# TCA785-V.net
KiCad netlist of a schematic drawn in Altium Designer
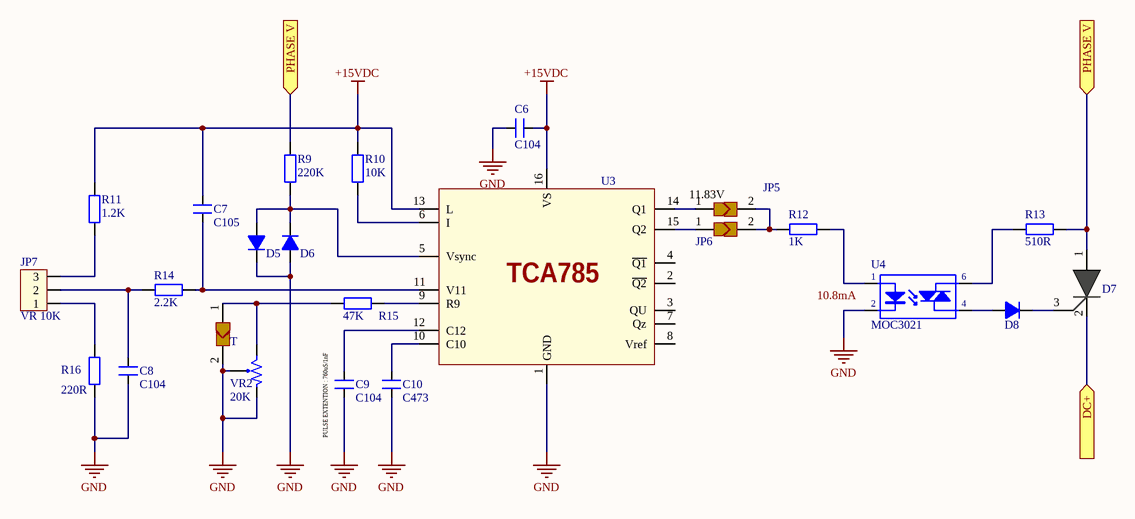
[diagram p0: TCA785-V.SchDoc]

(export (version "E")
  (design (tool "Eeschema 10.0.6"))
  (components
    (comp (ref "C6")
      (value "C104")
      (footprint "CN2-O")
      (description "CAP-gom")
      (libsource (lib "Sang_Library") (part "CAP-gom"))
    )
    (comp (ref "C7")
      (value "C105")
      (footprint "CN2-O")
      (description "CAP-gom")
      (libsource (lib "Sang_Library") (part "CAP-gom"))
    )
    (comp (ref "C8")
      (value "C104")
      (footprint "CN2-O")
      (description "CAP-gom")
      (libsource (lib "Sang_Library") (part "CAP-gom"))
    )
    (comp (ref "C9")
      (value "C104")
      (footprint "CN2-O")
      (description "CAP-gom")
      (libsource (lib "Sang_Library") (part "CAP-gom"))
    )
    (comp (ref "C10")
      (value "C473")
      (footprint "CN2-O")
      (description "CAP-gom")
      (libsource (lib "Sang_Library") (part "CAP-gom"))
    )
    (comp (ref "D5")
      (value "Diode  1N4007")
      (footprint "DO41-1A")
      (description "Diode 1A")
      (libsource (lib "Sang_Library") (part "Diode  1N4007"))
    )
    (comp (ref "D6")
      (value "Diode  1N4007")
      (footprint "DO41-1A")
      (description "Diode 1A")
      (libsource (lib "Sang_Library") (part "Diode  1N4007"))
    )
    (comp (ref "D7") (value "SCR") (footprint "TO-220") (libsource (lib "Huan") (part "BT151")))
    (comp (ref "D8")
      (value "Diode  1N4007")
      (footprint "DO41-1A")
      (description "Diode 1A")
      (libsource (lib "Sang_Library") (part "Diode  1N4007"))
    )
    (comp (ref "JP5")
      (value "PAD_Sellect")
      (footprint "PAD Select")
      (libsource (lib "Huan") (part "PAD_Sellect"))
    )
    (comp (ref "JP6")
      (value "PAD_Sellect")
      (footprint "PAD Select")
      (libsource (lib "Huan") (part "PAD_Sellect"))
    )
    (comp (ref "JP7")
      (value "VR 10K")
      (footprint "CON3")
      (description "Connector 3")
      (libsource (lib "syhaunguyen") (part "Con3"))
    )
    (comp (ref "R9")
      (value "220K")
      (footprint "R1/4W")
      (description "Resistor 1/4W")
      (libsource (lib "Sang_Library") (part "R1/4W"))
    )
    (comp (ref "R10")
      (value "10K")
      (footprint "R1/4W")
      (description "Resistor 1/4W")
      (libsource (lib "Sang_Library") (part "R1/4W"))
    )
    (comp (ref "R11")
      (value "1.2K")
      (footprint "R1/4W")
      (description "Resistor 1/4W")
      (libsource (lib "Sang_Library") (part "R1/4W"))
    )
    (comp (ref "R12")
      (value "1K")
      (footprint "R1/4W")
      (description "Resistor 1/4W")
      (libsource (lib "Sang_Library") (part "R1/4W"))
    )
    (comp (ref "R13")
      (value "510R")
      (footprint "R1/4W")
      (description "Resistor 1/4W")
      (libsource (lib "Sang_Library") (part "R1/4W"))
    )
    (comp (ref "R14")
      (value "2.2K")
      (footprint "R1/4W")
      (description "Resistor 1/4W")
      (libsource (lib "Sang_Library") (part "R1/4W"))
    )
    (comp (ref "R15")
      (value "47K")
      (footprint "R1/4W")
      (description "Resistor 1/4W")
      (libsource (lib "Sang_Library") (part "R1/4W"))
    )
    (comp (ref "R16")
      (value "220R")
      (footprint "R1/4W")
      (description "Resistor 1/4W")
      (libsource (lib "Sang_Library") (part "R1/4W"))
    )
    (comp (ref "T")
      (value "PAD_Sellect")
      (footprint "PAD Select")
      (libsource (lib "Huan") (part "PAD_Sellect"))
    )
    (comp (ref "U3") (value "TCA785Q") (footprint "DIP-16") (libsource (lib "Huan") (part "TCA785Q")))
    (comp (ref "U4")
      (value "MOC3021")
      (footprint "DIP6/W0.3 - MOC3021")
      (description "Single Opto")
      (libsource (lib "Sang_Library") (part "MOC3021"))
    )
    (comp (ref "VR2")
      (value "20K")
      (footprint "VR")
      (description "Var Resistor RM065")
      (libsource (lib "Sang_Library") (part "VR"))
    )
  )
  (nets
    (net (code "1") (name "+15VDC") (class "Default")
      (node (ref "C6") (pin "2") (pinfunction "2_2") (pintype "passive"))
      (node (ref "C7") (pin "2") (pinfunction "2_2") (pintype "passive"))
      (node (ref "R10") (pin "1") (pinfunction "1_1") (pintype "passive"))
      (node (ref "R11") (pin "2") (pinfunction "2_2") (pintype "passive"))
      (node (ref "U3") (pin "13") (pinfunction "L_13") (pintype "passive"))
      (node (ref "U3") (pin "16") (pinfunction "VS_16") (pintype "passive"))
    )
    (net (code "3") (name "/DC+") (class "Default")
      (node (ref "D7") (pin "2") (pinfunction "K_2") (pintype "passive"))
    )
    (net (code "4") (name "/PHASE V") (class "Default")
      (node (ref "D7") (pin "1") (pinfunction "A_1") (pintype "passive"))
      (node (ref "R13") (pin "1") (pinfunction "1_1") (pintype "passive"))
      (node (ref "R9") (pin "1") (pinfunction "1_1") (pintype "passive"))
    )
    (net (code "5") (name "GND") (class "Default")
      (node (ref "C10") (pin "1") (pinfunction "1_1") (pintype "passive"))
      (node (ref "C6") (pin "1") (pinfunction "1_1") (pintype "passive"))
      (node (ref "C8") (pin "1") (pinfunction "1_1") (pintype "passive"))
      (node (ref "C9") (pin "1") (pinfunction "1_1") (pintype "passive"))
      (node (ref "D5") (pin "2") (pinfunction "2_2") (pintype "passive"))
      (node (ref "D6") (pin "1") (pinfunction "1_1") (pintype "passive"))
      (node (ref "R16") (pin "1") (pinfunction "1_1") (pintype "passive"))
      (node (ref "T") (pin "2") (pinfunction "2_2") (pintype "passive"))
      (node (ref "U3") (pin "1") (pinfunction "GND_1") (pintype "passive"))
      (node (ref "U4") (pin "2") (pinfunction "K_2") (pintype "passive"))
      (node (ref "VR2") (pin "1") (pinfunction "1_1") (pintype "passive"))
      (node (ref "VR2") (pin "2") (pinfunction "2_2") (pintype "passive"))
    )
    (net (code "6") (name "Net-(C8-Pad2)") (class "Default")
      (node (ref "C8") (pin "2") (pinfunction "2_2") (pintype "passive"))
      (node (ref "JP7") (pin "2") (pinfunction "2_2") (pintype "passive"))
      (node (ref "R14") (pin "2") (pinfunction "2_2") (pintype "passive"))
    )
    (net (code "7") (name "Net-(D7-G)") (class "Default")
      (node (ref "D7") (pin "3") (pinfunction "G_3") (pintype "passive"))
      (node (ref "D8") (pin "2") (pinfunction "2_2") (pintype "passive"))
    )
    (net (code "8") (name "Net-(JP5-Pad2)") (class "Default")
      (node (ref "JP5") (pin "2") (pinfunction "2_2") (pintype "passive"))
      (node (ref "JP6") (pin "2") (pinfunction "2_2") (pintype "passive"))
      (node (ref "R12") (pin "2") (pinfunction "2_2") (pintype "passive"))
    )
    (net (code "9") (name "Net-(JP7-Pad1)") (class "Default")
      (node (ref "JP7") (pin "1") (pinfunction "1_1") (pintype "passive"))
      (node (ref "R16") (pin "2") (pinfunction "2_2") (pintype "passive"))
    )
    (net (code "10") (name "Net-(JP7-Pad3)") (class "Default")
      (node (ref "JP7") (pin "3") (pinfunction "3_3") (pintype "passive"))
      (node (ref "R11") (pin "1") (pinfunction "1_1") (pintype "passive"))
    )
    (net (code "11") (name "Net-(R15-Pad1)") (class "Default")
      (node (ref "R15") (pin "1") (pinfunction "1_1") (pintype "passive"))
      (node (ref "T") (pin "1") (pinfunction "1_1") (pintype "passive"))
      (node (ref "VR2") (pin "3") (pinfunction "3_3") (pintype "passive"))
    )
    (net (code "12") (name "Net-(U3-C10)") (class "Default")
      (node (ref "C10") (pin "2") (pinfunction "2_2") (pintype "passive"))
      (node (ref "U3") (pin "10") (pinfunction "C10_10") (pintype "passive"))
    )
    (net (code "13") (name "Net-(U3-C12)") (class "Default")
      (node (ref "C9") (pin "2") (pinfunction "2_2") (pintype "passive"))
      (node (ref "U3") (pin "12") (pinfunction "C12_12") (pintype "passive"))
    )
    (net (code "14") (name "Net-(U3-I)") (class "Default")
      (node (ref "R10") (pin "2") (pinfunction "2_2") (pintype "passive"))
      (node (ref "U3") (pin "6") (pinfunction "I_6") (pintype "passive"))
    )
    (net (code "15") (name "Net-(U3-Q1)") (class "Default")
      (node (ref "JP5") (pin "1") (pinfunction "1_1") (pintype "passive"))
      (node (ref "U3") (pin "14") (pinfunction "Q1_14") (pintype "passive"))
    )
    (net (code "16") (name "Net-(U3-Q2)") (class "Default")
      (node (ref "JP6") (pin "1") (pinfunction "1_1") (pintype "passive"))
      (node (ref "U3") (pin "15") (pinfunction "Q2_15") (pintype "passive"))
    )
    (net (code "17") (name "Net-(U3-R9)") (class "Default")
      (node (ref "R15") (pin "2") (pinfunction "2_2") (pintype "passive"))
      (node (ref "U3") (pin "9") (pinfunction "R9_9") (pintype "passive"))
    )
    (net (code "18") (name "Net-(U3-V11)") (class "Default")
      (node (ref "C7") (pin "1") (pinfunction "1_1") (pintype "passive"))
      (node (ref "R14") (pin "1") (pinfunction "1_1") (pintype "passive"))
      (node (ref "U3") (pin "11") (pinfunction "V11_11") (pintype "passive"))
    )
    (net (code "19") (name "Net-(U3-Vsync)") (class "Default")
      (node (ref "D5") (pin "1") (pinfunction "1_1") (pintype "passive"))
      (node (ref "D6") (pin "2") (pinfunction "2_2") (pintype "passive"))
      (node (ref "R9") (pin "2") (pinfunction "2_2") (pintype "passive"))
      (node (ref "U3") (pin "5") (pinfunction "Vsync_5") (pintype "passive"))
    )
    (net (code "20") (name "Net-(U4-A)") (class "Default")
      (node (ref "R12") (pin "1") (pinfunction "1_1") (pintype "passive"))
      (node (ref "U4") (pin "1") (pinfunction "A_1") (pintype "passive"))
    )
    (net (code "21") (name "Net-(U4-C)") (class "Default")
      (node (ref "R13") (pin "2") (pinfunction "2_2") (pintype "passive"))
      (node (ref "U4") (pin "6") (pinfunction "C_6") (pintype "passive"))
    )
    (net (code "22") (name "Net-(U4-E)") (class "Default")
      (node (ref "D8") (pin "1") (pinfunction "1_1") (pintype "passive"))
      (node (ref "U4") (pin "4") (pinfunction "E_4") (pintype "passive"))
    )
    (net (code "23") (name "unconnected-(U3-QU-Pad3)") (class "Default")
      (node (ref "U3") (pin "3") (pinfunction "QU_3") (pintype "passive"))
    )
    (net (code "24") (name "unconnected-(U3-Qz-Pad7)") (class "Default")
      (node (ref "U3") (pin "7") (pinfunction "Qz_7") (pintype "passive"))
    )
    (net (code "25") (name "unconnected-(U3-Vref-Pad8)") (class "Default")
      (node (ref "U3") (pin "8") (pinfunction "Vref_8") (pintype "passive"))
    )
    (net (code "26") (name "unconnected-(U3-~{Q1}-Pad4)") (class "Default")
      (node (ref "U3") (pin "4") (pinfunction "~{Q1}_4") (pintype "passive"))
    )
    (net (code "27") (name "unconnected-(U3-~{Q2}-Pad2)") (class "Default")
      (node (ref "U3") (pin "2") (pinfunction "~{Q2}_2") (pintype "passive"))
    )
  )
)
